# unicorn_1.net
KiCad netlist of a schematic drawn in Altium Designer
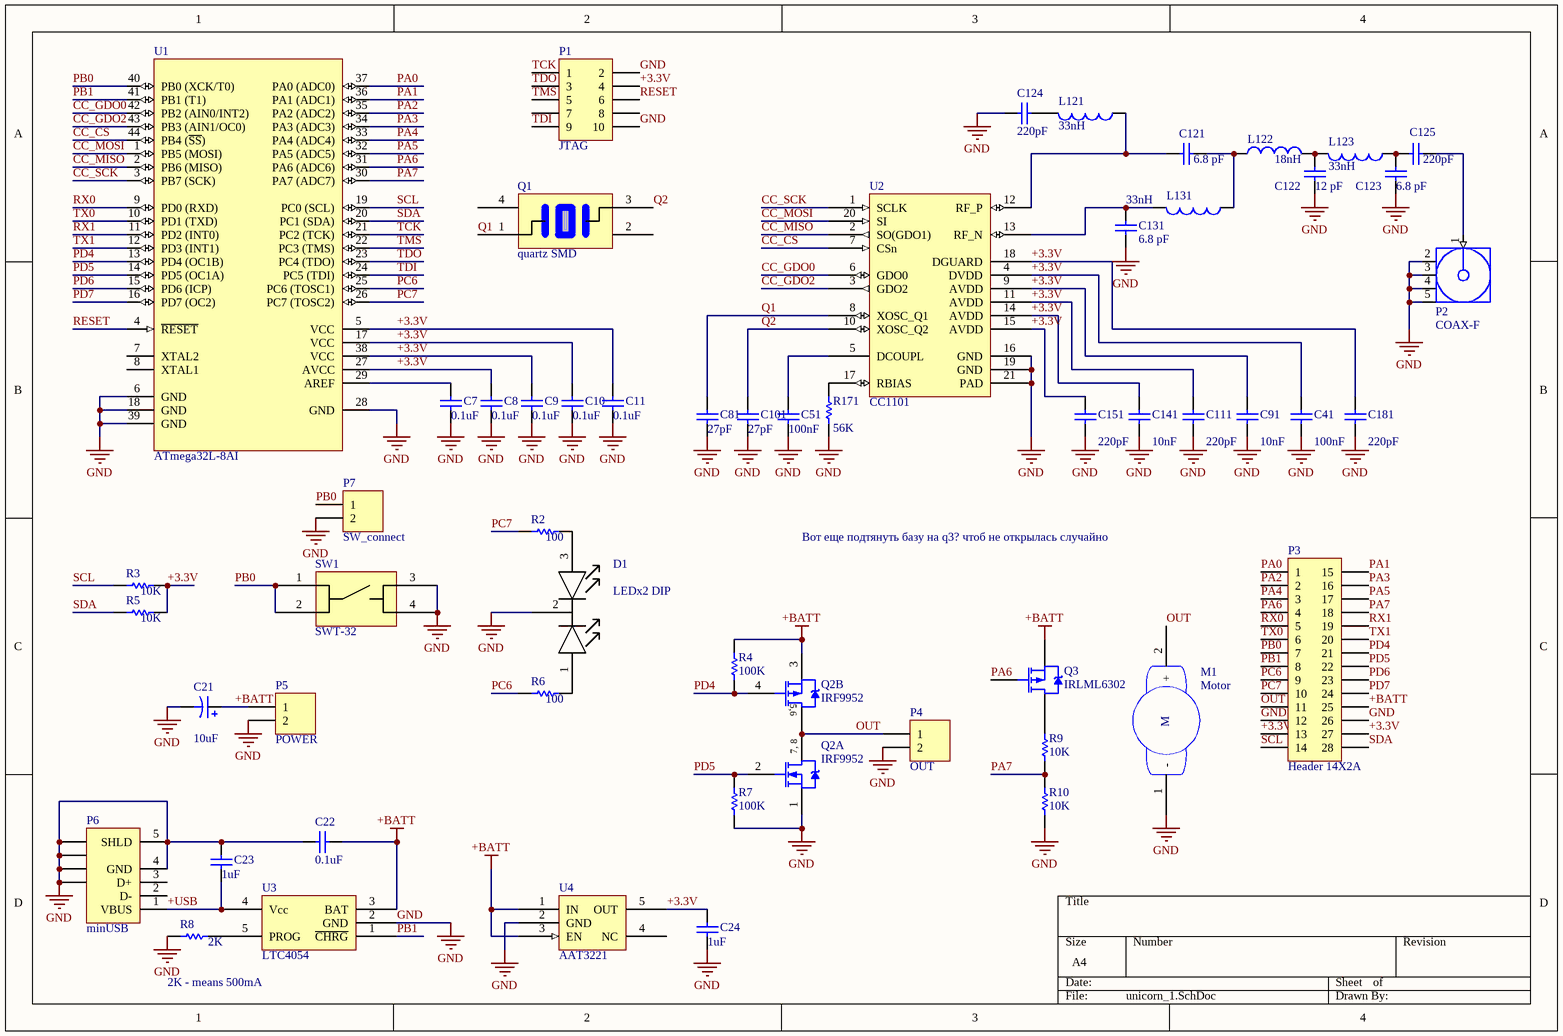
[diagram p0: unicorn_1.SchDoc]

(export (version "E")
  (design (tool "Eeschema 10.0.6"))
  (components
    (comp (ref "C7")
      (value "0.1uF")
      (footprint "CAPC1005L")
      (description "Capacitor (Semiconductor SIM Model)")
      (fields (field (name "Comment") "Cap Semi") (field (name "PUBLISHER") "Altium Limited"))
      (libsource (lib "Miscellaneous Devices") (part "Cap Semi"))
    )
    (comp (ref "C8")
      (value "0.1uF")
      (footprint "CAPC1005L")
      (description "Capacitor (Semiconductor SIM Model)")
      (fields (field (name "Comment") "Cap Semi") (field (name "PUBLISHER") "Altium Limited"))
      (libsource (lib "Miscellaneous Devices") (part "Cap Semi"))
    )
    (comp (ref "C9")
      (value "0.1uF")
      (footprint "CAPC1005L")
      (description "Capacitor (Semiconductor SIM Model)")
      (fields (field (name "Comment") "Cap Semi") (field (name "PUBLISHER") "Altium Limited"))
      (libsource (lib "Miscellaneous Devices") (part "Cap Semi"))
    )
    (comp (ref "C10")
      (value "0.1uF")
      (footprint "CAPC1005L")
      (description "Capacitor (Semiconductor SIM Model)")
      (fields (field (name "Comment") "Cap Semi") (field (name "PUBLISHER") "Altium Limited"))
      (libsource (lib "Miscellaneous Devices") (part "Cap Semi"))
    )
    (comp (ref "C11")
      (value "0.1uF")
      (footprint "CAPC1005L")
      (description "Capacitor (Semiconductor SIM Model)")
      (fields (field (name "Comment") "Cap Semi") (field (name "PUBLISHER") "Altium Limited"))
      (libsource (lib "Miscellaneous Devices") (part "Cap Semi"))
    )
    (comp (ref "C21")
      (value "10uF")
      (footprint "CAPC2012L")
      (description "Polarized Capacitor (Surface Mount)")
      (fields (field (name "Comment") "Cap Pol3") (field (name "PUBLISHER") "Altium Limited"))
      (libsource (lib "Miscellaneous Devices") (part "Cap Pol3"))
    )
    (comp (ref "C22")
      (value "0.1uF")
      (footprint "CAPC1005L")
      (description "Capacitor (Semiconductor SIM Model)")
      (fields (field (name "Comment") "Cap Semi") (field (name "PUBLISHER") "Altium Limited"))
      (libsource (lib "Miscellaneous Devices") (part "Cap Semi"))
    )
    (comp (ref "C23")
      (value "1uF")
      (footprint "CAPC1608L")
      (description "Capacitor (Semiconductor SIM Model)")
      (fields (field (name "Comment") "Cap Semi") (field (name "PUBLISHER") "Altium Limited"))
      (libsource (lib "Miscellaneous Devices") (part "Cap Semi"))
    )
    (comp (ref "C24")
      (value "1uF")
      (footprint "CAPC1608L")
      (description "Capacitor (Semiconductor SIM Model)")
      (fields (field (name "Comment") "Cap Semi") (field (name "PUBLISHER") "Altium Limited"))
      (libsource (lib "Miscellaneous Devices") (part "Cap Semi"))
    )
    (comp (ref "C41")
      (value "100nF")
      (footprint "CAPC1005L")
      (description "Capacitor (Semiconductor SIM Model)")
      (fields (field (name "Comment") "Cap Semi") (field (name "PUBLISHER") "Altium Limited"))
      (libsource (lib "Miscellaneous Devices") (part "Cap Semi"))
    )
    (comp (ref "C51")
      (value "100nF")
      (footprint "CAPC1005L")
      (description "Capacitor (Semiconductor SIM Model)")
      (fields (field (name "Comment") "Cap Semi") (field (name "PUBLISHER") "Altium Limited"))
      (libsource (lib "Miscellaneous Devices") (part "Cap Semi"))
    )
    (comp (ref "C81")
      (value "27pF")
      (footprint "CAPC1005L")
      (description "Capacitor (Semiconductor SIM Model)")
      (fields (field (name "Comment") "Cap Semi") (field (name "PUBLISHER") "Altium Limited"))
      (libsource (lib "Miscellaneous Devices") (part "Cap Semi"))
    )
    (comp (ref "C91")
      (value "10nF")
      (footprint "CAPC1005L")
      (description "Capacitor (Semiconductor SIM Model)")
      (fields (field (name "Comment") "Cap Semi") (field (name "PUBLISHER") "Altium Limited"))
      (libsource (lib "Miscellaneous Devices") (part "Cap Semi"))
    )
    (comp (ref "C101")
      (value "27pF")
      (footprint "CAPC1005L")
      (description "Capacitor (Semiconductor SIM Model)")
      (fields (field (name "Comment") "Cap Semi") (field (name "PUBLISHER") "Altium Limited"))
      (libsource (lib "Miscellaneous Devices") (part "Cap Semi"))
    )
    (comp (ref "C111")
      (value "220pF")
      (footprint "CAPC1005L")
      (description "Capacitor (Semiconductor SIM Model)")
      (fields (field (name "Comment") "Cap Semi") (field (name "PUBLISHER") "Altium Limited"))
      (libsource (lib "Miscellaneous Devices") (part "Cap Semi"))
    )
    (comp (ref "C121")
      (value "6.8 pF")
      (footprint "CAPC1005L")
      (description "Capacitor (Semiconductor SIM Model)")
      (fields (field (name "Comment") "Cap Semi") (field (name "PUBLISHER") "Altium Limited"))
      (libsource (lib "Miscellaneous Devices") (part "Cap Semi"))
    )
    (comp (ref "C122")
      (value "12 pF")
      (footprint "CAPC1005L")
      (description "Capacitor (Semiconductor SIM Model)")
      (fields (field (name "Comment") "Cap Semi") (field (name "PUBLISHER") "Altium Limited"))
      (libsource (lib "Miscellaneous Devices") (part "Cap Semi"))
    )
    (comp (ref "C123")
      (value "6.8 pF")
      (footprint "CAPC1005L")
      (description "Capacitor (Semiconductor SIM Model)")
      (fields (field (name "Comment") "Cap Semi") (field (name "PUBLISHER") "Altium Limited"))
      (libsource (lib "Miscellaneous Devices") (part "Cap Semi"))
    )
    (comp (ref "C124")
      (value "220pF")
      (footprint "CAPC1005L")
      (description "Capacitor (Semiconductor SIM Model)")
      (fields (field (name "Comment") "Cap Semi") (field (name "PUBLISHER") "Altium Limited"))
      (libsource (lib "Miscellaneous Devices") (part "Cap Semi"))
    )
    (comp (ref "C125")
      (value "220pF")
      (footprint "CAPC1005L")
      (description "Capacitor (Semiconductor SIM Model)")
      (fields (field (name "Comment") "Cap Semi") (field (name "PUBLISHER") "Altium Limited"))
      (libsource (lib "Miscellaneous Devices") (part "Cap Semi"))
    )
    (comp (ref "C131")
      (value "6.8 pF")
      (footprint "CAPC1005L")
      (description "Capacitor (Semiconductor SIM Model)")
      (fields (field (name "Comment") "Cap Semi") (field (name "PUBLISHER") "Altium Limited"))
      (libsource (lib "Miscellaneous Devices") (part "Cap Semi"))
    )
    (comp (ref "C141")
      (value "10nF")
      (footprint "CAPC1005L")
      (description "Capacitor (Semiconductor SIM Model)")
      (fields (field (name "Comment") "Cap Semi") (field (name "PUBLISHER") "Altium Limited"))
      (libsource (lib "Miscellaneous Devices") (part "Cap Semi"))
    )
    (comp (ref "C151")
      (value "220pF")
      (footprint "CAPC1005L")
      (description "Capacitor (Semiconductor SIM Model)")
      (fields (field (name "Comment") "Cap Semi") (field (name "PUBLISHER") "Altium Limited"))
      (libsource (lib "Miscellaneous Devices") (part "Cap Semi"))
    )
    (comp (ref "C181")
      (value "220pF")
      (footprint "CAPC1005L")
      (description "Capacitor (Semiconductor SIM Model)")
      (fields (field (name "Comment") "Cap Semi") (field (name "PUBLISHER") "Altium Limited"))
      (libsource (lib "Miscellaneous Devices") (part "Cap Semi"))
    )
    (comp (ref "D1")
      (value "LEDx2 DIP")
      (footprint "LEDx2")
      (description "in DIP")
      (libsource (lib "uni_Library") (part "LEDx2"))
    )
    (comp (ref "L121")
      (value "33nH")
      (footprint "INDC1005AL")
      (description "Inductor")
      (fields (field (name "PUBLISHER") "Altium Limited"))
      (libsource (lib "Miscellaneous Devices") (part "Inductor"))
    )
    (comp (ref "L122")
      (value "18nH")
      (footprint "INDC1005AL")
      (description "Inductor")
      (fields (field (name "PUBLISHER") "Altium Limited"))
      (libsource (lib "Miscellaneous Devices") (part "Inductor"))
    )
    (comp (ref "L123")
      (value "33nH")
      (footprint "INDC1005AL")
      (description "Inductor")
      (fields (field (name "PUBLISHER") "Altium Limited"))
      (libsource (lib "Miscellaneous Devices") (part "Inductor"))
    )
    (comp (ref "L131")
      (value "33nH")
      (footprint "INDC1005AL")
      (description "Inductor")
      (fields (field (name "PUBLISHER") "Altium Limited"))
      (libsource (lib "Miscellaneous Devices") (part "Inductor"))
    )
    (comp (ref "M1") (value "Motor") (footprint "Motor") (libsource (lib "uni_Library") (part "Motor")))
    (comp (ref "P1")
      (value "JTAG")
      (footprint "HDR2X5")
      (description "Header, 5-Pin, Dual row")
      (fields (field (name "PUBLISHER") "Altium Limited"))
      (libsource (lib "Miscellaneous Connectors") (part "Header 5X2"))
    )
    (comp (ref "P2")
      (value "COAX-F")
      (footprint "MCX5.08-H5")
      (fields (field (name "PUBLISHER") "Altium Limited"))
      (libsource (lib "Miscellaneous Connectors") (part "COAX-F"))
    )
    (comp (ref "P3")
      (value "Header 14X2A")
      (footprint "HDR2X14_CEN")
      (description "Header, 14-Pin, Dual row")
      (fields (field (name "PUBLISHER") "Altium Limited"))
      (libsource (lib "Miscellaneous Connectors") (part "Header 14X2A"))
    )
    (comp (ref "P4")
      (value "OUT")
      (footprint "HDR1X2H")
      (description "Header, 2-Pin, Right Angle")
      (fields (field (name "PUBLISHER") "Altium Limited"))
      (libsource (lib "Miscellaneous Connectors") (part "Header 2H"))
    )
    (comp (ref "P5")
      (value "POWER")
      (footprint "HDR1X2H")
      (description "Header, 2-Pin, Right Angle")
      (fields (field (name "PUBLISHER") "Altium Limited"))
      (libsource (lib "Miscellaneous Connectors") (part "Header 2H"))
    )
    (comp (ref "P6")
      (value "minUSB")
      (footprint "440479")
      (description "USB 2.0, Right Angle, SMT, A Type, Receptacle, 5 Position, Black")
      (fields (field (name "PUBLISHER") "Altium Limited"))
      (libsource (lib "AMP Serial Bus USB") (part "440478-2"))
    )
    (comp (ref "P7")
      (value "SW_connect")
      (footprint "HDR1X2")
      (description "Header, 2-Pin")
      (fields (field (name "PUBLISHER") "Altium Limited"))
      (libsource (lib "Miscellaneous Connectors") (part "Header 2"))
    )
    (comp (ref "Q1")
      (value "quartz SMD")
      (footprint "quartz_pattern")
      (description "в корпусе 0532")
      (libsource (lib "uni_Library") (part "qartz 0532"))
    )
    (comp (ref "Q2")
      (value "IRF9952")
      (footprint "SO-8_N")
      (description "HEXFET Power MOSFET")
      (fields (field (name "PUBLISHER") "Altium Limited"))
      (libsource (lib "IR Discrete MOSFET - Power") (part "IRF9952"))
    )
    (comp (ref "Q3")
      (value "IRLML6302")
      (footprint "SOT-23")
      (description "HEXFET Power MOSFET")
      (fields (field (name "PUBLISHER") "Altium Limited"))
      (libsource (lib "IR Discrete MOSFET - Power") (part "IRLML6302"))
    )
    (comp (ref "R2")
      (value "100")
      (footprint "RESC1005L")
      (description "Semiconductor Resistor")
      (fields (field (name "Comment") "Res Semi") (field (name "PUBLISHER") "Altium Limited"))
      (libsource (lib "Miscellaneous Devices") (part "Res Semi"))
    )
    (comp (ref "R3")
      (value "10K")
      (footprint "RESC1005L")
      (description "Semiconductor Resistor")
      (fields (field (name "Comment") "Res Semi") (field (name "PUBLISHER") "Altium Limited"))
      (libsource (lib "Miscellaneous Devices") (part "Res Semi"))
    )
    (comp (ref "R4")
      (value "100K")
      (footprint "RESC1005L")
      (description "Semiconductor Resistor")
      (fields (field (name "Comment") "Res Semi") (field (name "PUBLISHER") "Altium Limited"))
      (libsource (lib "Miscellaneous Devices") (part "Res Semi"))
    )
    (comp (ref "R5")
      (value "10K")
      (footprint "RESC1005L")
      (description "Semiconductor Resistor")
      (fields (field (name "Comment") "Res Semi") (field (name "PUBLISHER") "Altium Limited"))
      (libsource (lib "Miscellaneous Devices") (part "Res Semi"))
    )
    (comp (ref "R6")
      (value "100")
      (footprint "RESC1005L")
      (description "Semiconductor Resistor")
      (fields (field (name "Comment") "Res Semi") (field (name "PUBLISHER") "Altium Limited"))
      (libsource (lib "Miscellaneous Devices") (part "Res Semi"))
    )
    (comp (ref "R7")
      (value "100K")
      (footprint "RESC1005L")
      (description "Semiconductor Resistor")
      (fields (field (name "Comment") "Res Semi") (field (name "PUBLISHER") "Altium Limited"))
      (libsource (lib "Miscellaneous Devices") (part "Res Semi"))
    )
    (comp (ref "R8")
      (value "2K")
      (footprint "RESC1005L")
      (description "Semiconductor Resistor")
      (fields (field (name "Comment") "Res Semi") (field (name "PUBLISHER") "Altium Limited"))
      (libsource (lib "Miscellaneous Devices") (part "Res Semi"))
    )
    (comp (ref "R9")
      (value "10K")
      (footprint "RESC1005L")
      (description "Semiconductor Resistor")
      (fields (field (name "Comment") "Res Semi") (field (name "PUBLISHER") "Altium Limited"))
      (libsource (lib "Miscellaneous Devices") (part "Res Semi"))
    )
    (comp (ref "R10")
      (value "10K")
      (footprint "RESC1005L")
      (description "Semiconductor Resistor")
      (fields (field (name "Comment") "Res Semi") (field (name "PUBLISHER") "Altium Limited"))
      (libsource (lib "Miscellaneous Devices") (part "Res Semi"))
    )
    (comp (ref "R171")
      (value "56K")
      (footprint "RESC1005L")
      (description "Semiconductor Resistor")
      (fields (field (name "Comment") "Res Semi") (field (name "PUBLISHER") "Altium Limited"))
      (libsource (lib "Miscellaneous Devices") (part "Res Semi"))
    )
    (comp (ref "SW1")
      (value "SWT-32")
      (footprint "SWT-32 pattern")
      (description "Кнопка тактова , поверхностный монтаж")
      (libsource (lib "uni_Library") (part "SWT-32"))
    )
    (comp (ref "U1")
      (value "ATmega32L-8AI")
      (footprint "44A_L")
      (description "8-Bit AVR Microcontroller with 32K Bytes of In-System Programmable Flash Memory")
      (fields (field (name "PUBLISHER") "Altium Limited"))
      (libsource (lib "Atmel Microcontroller 8-Bit AVR") (part "ATmega32L-8AI"))
    )
    (comp (ref "U2")
      (value "CC1101")
      (footprint "QFN50P397X397X80-20N")
      (description "Low-Power Sub-1 GHz RF Transceiver")
      (libsource (lib "uni_Library") (part "CC1101"))
    )
    (comp (ref "U3")
      (value "LTC4054")
      (footprint "SOT95P270X100-5N")
      (description "Standalone Linear  Li-Ion Battery Charger with  Thermal Regulation in ThinSOT")
      (libsource (lib "uni_Library") (part "LTC4054"))
    )
    (comp (ref "U4")
      (value "AAT3221")
      (footprint "SOT95P280X145-5N")
      (description "PowerLinear NanoPower low   dropout (LDO) linear regulator.")
      (libsource (lib "uni_Library") (part "AAT3221"))
    )
  )
  (nets
    (net (code "1") (name "+BATT") (class "Default")
      (node (ref "C21") (pin "1") (pinfunction "1_1") (pintype "passive"))
      (node (ref "C22") (pin "2") (pinfunction "2_2") (pintype "passive"))
      (node (ref "P3") (pin "25") (pinfunction "25_25") (pintype "passive"))
      (node (ref "P5") (pin "1") (pinfunction "1_1") (pintype "passive"))
      (node (ref "Q2") (pin "3") (pinfunction "S2_3") (pintype "passive"))
      (node (ref "Q3") (pin "2") (pinfunction "S_2") (pintype "passive"))
      (node (ref "R4") (pin "1") (pinfunction "1_1") (pintype "passive"))
      (node (ref "U3") (pin "3") (pinfunction "BAT_3") (pintype "passive"))
      (node (ref "U4") (pin "1") (pinfunction "IN_1") (pintype "power_in"))
      (node (ref "U4") (pin "3") (pinfunction "EN_3") (pintype "input"))
    )
    (net (code "2") (name "/+3.3V") (class "Default")
      (node (ref "C10") (pin "1") (pinfunction "1_1") (pintype "passive"))
      (node (ref "C11") (pin "1") (pinfunction "1_1") (pintype "passive"))
      (node (ref "C111") (pin "2") (pinfunction "2_2") (pintype "passive"))
      (node (ref "C141") (pin "2") (pinfunction "2_2") (pintype "passive"))
      (node (ref "C151") (pin "2") (pinfunction "2_2") (pintype "passive"))
      (node (ref "C181") (pin "2") (pinfunction "2_2") (pintype "passive"))
      (node (ref "C24") (pin "1") (pinfunction "1_1") (pintype "passive"))
      (node (ref "C41") (pin "2") (pinfunction "2_2") (pintype "passive"))
      (node (ref "C8") (pin "1") (pinfunction "1_1") (pintype "passive"))
      (node (ref "C9") (pin "1") (pinfunction "1_1") (pintype "passive"))
      (node (ref "C91") (pin "2") (pinfunction "2_2") (pintype "passive"))
      (node (ref "P1") (pin "4") (pinfunction "4_4") (pintype "passive"))
      (node (ref "P3") (pin "13") (pinfunction "13_13") (pintype "passive"))
      (node (ref "P3") (pin "27") (pinfunction "27_27") (pintype "passive"))
      (node (ref "R3") (pin "1") (pinfunction "1_1") (pintype "passive"))
      (node (ref "R5") (pin "1") (pinfunction "1_1") (pintype "passive"))
      (node (ref "U1") (pin "17") (pinfunction "VCC_17") (pintype "power_in"))
      (node (ref "U1") (pin "27") (pinfunction "AVCC_27") (pintype "power_in"))
      (node (ref "U1") (pin "38") (pinfunction "VCC_38") (pintype "power_in"))
      (node (ref "U1") (pin "5") (pinfunction "VCC_5") (pintype "power_in"))
      (node (ref "U2") (pin "11") (pinfunction "AVDD_11") (pintype "power_in"))
      (node (ref "U2") (pin "14") (pinfunction "AVDD_14") (pintype "power_in"))
      (node (ref "U2") (pin "15") (pinfunction "AVDD_15") (pintype "power_in"))
      (node (ref "U2") (pin "18") (pinfunction "DGUARD_18") (pintype "power_in"))
      (node (ref "U2") (pin "4") (pinfunction "DVDD_4") (pintype "power_in"))
      (node (ref "U2") (pin "9") (pinfunction "AVDD_9") (pintype "power_in"))
      (node (ref "U4") (pin "5") (pinfunction "OUT_5") (pintype "power_in"))
    )
    (net (code "3") (name "/+USB") (class "Default")
      (node (ref "C23") (pin "2") (pinfunction "2_2") (pintype "passive"))
      (node (ref "P6") (pin "1") (pinfunction "VBUS_1") (pintype "power_in"))
      (node (ref "U3") (pin "4") (pinfunction "Vcc_4") (pintype "passive"))
    )
    (net (code "4") (name "/CC_CS") (class "Default")
      (node (ref "U1") (pin "44") (pinfunction "PB4_(~{SS})_44") (pintype "bidirectional"))
      (node (ref "U2") (pin "7") (pinfunction "CSn_7") (pintype "input"))
    )
    (net (code "5") (name "/CC_GDO0") (class "Default")
      (node (ref "U1") (pin "42") (pinfunction "PB2_(AIN0/INT2)_42") (pintype "bidirectional"))
      (node (ref "U2") (pin "6") (pinfunction "GDO0_6") (pintype "bidirectional"))
    )
    (net (code "6") (name "/CC_GDO2") (class "Default")
      (node (ref "U1") (pin "43") (pinfunction "PB3_(AIN1/OC0)_43") (pintype "bidirectional"))
      (node (ref "U2") (pin "3") (pinfunction "GDO2_3") (pintype "output"))
    )
    (net (code "7") (name "/CC_MISO") (class "Default")
      (node (ref "U1") (pin "2") (pinfunction "PB6_(MISO)_2") (pintype "bidirectional"))
      (node (ref "U2") (pin "2") (pinfunction "SO(GDO1)_2") (pintype "output"))
    )
    (net (code "8") (name "/CC_MOSI") (class "Default")
      (node (ref "U1") (pin "1") (pinfunction "PB5_(MOSI)_1") (pintype "bidirectional"))
      (node (ref "U2") (pin "20") (pinfunction "SI_20") (pintype "input"))
    )
    (net (code "9") (name "/CC_SCK") (class "Default")
      (node (ref "U1") (pin "3") (pinfunction "PB7_(SCK)_3") (pintype "bidirectional"))
      (node (ref "U2") (pin "1") (pinfunction "SCLK_1") (pintype "input"))
    )
    (net (code "10") (name "/OUT") (class "Default")
      (node (ref "M1") (pin "2") (pinfunction "+_2") (pintype "passive"))
      (node (ref "P3") (pin "11") (pinfunction "11_11") (pintype "passive"))
      (node (ref "P4") (pin "1") (pinfunction "1_1") (pintype "passive"))
      (node (ref "Q2") (pin "5") (pinfunction "D2_5") (pintype "passive"))
      (node (ref "Q2") (pin "6") (pinfunction "D2_6") (pintype "passive"))
      (node (ref "Q2") (pin "7") (pinfunction "D1_7") (pintype "passive"))
      (node (ref "Q2") (pin "8") (pinfunction "D1_8") (pintype "passive"))
    )
    (net (code "11") (name "/PA0") (class "Default")
      (node (ref "P3") (pin "1") (pinfunction "1_1") (pintype "passive"))
      (node (ref "U1") (pin "37") (pinfunction "PA0_(ADC0)_37") (pintype "bidirectional"))
    )
    (net (code "12") (name "/PA1") (class "Default")
      (node (ref "P3") (pin "15") (pinfunction "15_15") (pintype "passive"))
      (node (ref "U1") (pin "36") (pinfunction "PA1_(ADC1)_36") (pintype "bidirectional"))
    )
    (net (code "13") (name "/PA2") (class "Default")
      (node (ref "P3") (pin "2") (pinfunction "2_2") (pintype "passive"))
      (node (ref "U1") (pin "35") (pinfunction "PA2_(ADC2)_35") (pintype "bidirectional"))
    )
    (net (code "14") (name "/PA3") (class "Default")
      (node (ref "P3") (pin "16") (pinfunction "16_16") (pintype "passive"))
      (node (ref "U1") (pin "34") (pinfunction "PA3_(ADC3)_34") (pintype "bidirectional"))
    )
    (net (code "15") (name "/PA4") (class "Default")
      (node (ref "P3") (pin "3") (pinfunction "3_3") (pintype "passive"))
      (node (ref "U1") (pin "33") (pinfunction "PA4_(ADC4)_33") (pintype "bidirectional"))
    )
    (net (code "16") (name "/PA5") (class "Default")
      (node (ref "P3") (pin "17") (pinfunction "17_17") (pintype "passive"))
      (node (ref "U1") (pin "32") (pinfunction "PA5_(ADC5)_32") (pintype "bidirectional"))
    )
    (net (code "17") (name "/PA6") (class "Default")
      (node (ref "P3") (pin "4") (pinfunction "4_4") (pintype "passive"))
      (node (ref "Q3") (pin "1") (pinfunction "G_1") (pintype "passive"))
      (node (ref "U1") (pin "31") (pinfunction "PA6_(ADC6)_31") (pintype "bidirectional"))
    )
    (net (code "18") (name "/PA7") (class "Default")
      (node (ref "P3") (pin "18") (pinfunction "18_18") (pintype "passive"))
      (node (ref "R10") (pin "1") (pinfunction "1_1") (pintype "passive"))
      (node (ref "R9") (pin "2") (pinfunction "2_2") (pintype "passive"))
      (node (ref "U1") (pin "30") (pinfunction "PA7_(ADC7)_30") (pintype "bidirectional"))
    )
    (net (code "19") (name "/PB0") (class "Default")
      (node (ref "P3") (pin "7") (pinfunction "7_7") (pintype "passive"))
      (node (ref "P7") (pin "1") (pinfunction "1_1") (pintype "passive"))
      (node (ref "SW1") (pin "1") (pintype "passive"))
      (node (ref "SW1") (pin "2") (pintype "passive"))
      (node (ref "U1") (pin "40") (pinfunction "PB0_(XCK/T0)_40") (pintype "bidirectional"))
    )
    (net (code "20") (name "/PB1") (class "Default")
      (node (ref "P3") (pin "8") (pinfunction "8_8") (pintype "passive"))
      (node (ref "U1") (pin "41") (pinfunction "PB1_(T1)_41") (pintype "bidirectional"))
      (node (ref "U3") (pin "1") (pinfunction "~{CHRG}_1") (pintype "passive"))
    )
    (net (code "21") (name "/PC6") (class "Default")
      (node (ref "P3") (pin "9") (pinfunction "9_9") (pintype "passive"))
      (node (ref "R6") (pin "2") (pinfunction "2_2") (pintype "passive"))
      (node (ref "U1") (pin "25") (pinfunction "PC6_(TOSC1)_25") (pintype "bidirectional"))
    )
    (net (code "22") (name "/PC7") (class "Default")
      (node (ref "P3") (pin "10") (pinfunction "10_10") (pintype "passive"))
      (node (ref "R2") (pin "2") (pinfunction "2_2") (pintype "passive"))
      (node (ref "U1") (pin "26") (pinfunction "PC7_(TOSC2)_26") (pintype "bidirectional"))
    )
    (net (code "23") (name "/PD4") (class "Default")
      (node (ref "P3") (pin "21") (pinfunction "21_21") (pintype "passive"))
      (node (ref "Q2") (pin "4") (pinfunction "G2_4") (pintype "passive"))
      (node (ref "R4") (pin "2") (pinfunction "2_2") (pintype "passive"))
      (node (ref "U1") (pin "13") (pinfunction "PD4_(OC1B)_13") (pintype "bidirectional"))
    )
    (net (code "24") (name "/PD5") (class "Default")
      (node (ref "P3") (pin "22") (pinfunction "22_22") (pintype "passive"))
      (node (ref "Q2") (pin "2") (pinfunction "G1_2") (pintype "passive"))
      (node (ref "R7") (pin "1") (pinfunction "1_1") (pintype "passive"))
      (node (ref "U1") (pin "14") (pinfunction "PD5_(OC1A)_14") (pintype "bidirectional"))
    )
    (net (code "25") (name "/PD6") (class "Default")
      (node (ref "P3") (pin "23") (pinfunction "23_23") (pintype "passive"))
      (node (ref "U1") (pin "15") (pinfunction "PD6_(ICP)_15") (pintype "bidirectional"))
    )
    (net (code "26") (name "/PD7") (class "Default")
      (node (ref "P3") (pin "24") (pinfunction "24_24") (pintype "passive"))
      (node (ref "U1") (pin "16") (pinfunction "PD7_(OC2)_16") (pintype "bidirectional"))
    )
    (net (code "27") (name "/Q1") (class "Default")
      (node (ref "C81") (pin "2") (pinfunction "2_2") (pintype "passive"))
      (node (ref "Q1") (pin "1") (pintype "passive"))
      (node (ref "U2") (pin "8") (pinfunction "XOSC_Q1_8") (pintype "bidirectional"))
    )
    (net (code "28") (name "/Q2") (class "Default")
      (node (ref "C101") (pin "2") (pinfunction "2_2") (pintype "passive"))
      (node (ref "Q1") (pin "3") (pintype "passive"))
      (node (ref "U2") (pin "10") (pinfunction "XOSC_Q2_10") (pintype "bidirectional"))
    )
    (net (code "29") (name "/RESET") (class "Default")
      (node (ref "P1") (pin "6") (pinfunction "6_6") (pintype "passive"))
      (node (ref "U1") (pin "4") (pinfunction "~{RESET}_4") (pintype "input"))
    )
    (net (code "30") (name "/RX0") (class "Default")
      (node (ref "P3") (pin "5") (pinfunction "5_5") (pintype "passive"))
      (node (ref "U1") (pin "9") (pinfunction "PD0_(RXD)_9") (pintype "bidirectional"))
    )
    (net (code "31") (name "/RX1") (class "Default")
      (node (ref "P3") (pin "19") (pinfunction "19_19") (pintype "passive"))
      (node (ref "U1") (pin "11") (pinfunction "PD2_(INT0)_11") (pintype "bidirectional"))
    )
    (net (code "32") (name "/SCL") (class "Default")
      (node (ref "P3") (pin "14") (pinfunction "14_14") (pintype "passive"))
      (node (ref "R3") (pin "2") (pinfunction "2_2") (pintype "passive"))
      (node (ref "U1") (pin "19") (pinfunction "PC0_(SCL)_19") (pintype "bidirectional"))
    )
    (net (code "33") (name "/SDA") (class "Default")
      (node (ref "P3") (pin "28") (pinfunction "28_28") (pintype "passive"))
      (node (ref "R5") (pin "2") (pinfunction "2_2") (pintype "passive"))
      (node (ref "U1") (pin "20") (pinfunction "PC1_(SDA)_20") (pintype "bidirectional"))
    )
    (net (code "34") (name "/TCK") (class "Default")
      (node (ref "P1") (pin "1") (pinfunction "1_1") (pintype "passive"))
      (node (ref "U1") (pin "21") (pinfunction "PC2_(TCK)_21") (pintype "bidirectional"))
    )
    (net (code "35") (name "/TDI") (class "Default")
      (node (ref "P1") (pin "9") (pinfunction "9_9") (pintype "passive"))
      (node (ref "U1") (pin "24") (pinfunction "PC5_(TDI)_24") (pintype "bidirectional"))
    )
    (net (code "36") (name "/TDO") (class "Default")
      (node (ref "P1") (pin "3") (pinfunction "3_3") (pintype "passive"))
      (node (ref "U1") (pin "23") (pinfunction "PC4_(TDO)_23") (pintype "bidirectional"))
    )
    (net (code "37") (name "/TMS") (class "Default")
      (node (ref "P1") (pin "5") (pinfunction "5_5") (pintype "passive"))
      (node (ref "U1") (pin "22") (pinfunction "PC3_(TMS)_22") (pintype "bidirectional"))
    )
    (net (code "38") (name "/TX0") (class "Default")
      (node (ref "P3") (pin "6") (pinfunction "6_6") (pintype "passive"))
      (node (ref "U1") (pin "10") (pinfunction "PD1_(TXD)_10") (pintype "bidirectional"))
    )
    (net (code "39") (name "/TX1") (class "Default")
      (node (ref "P3") (pin "20") (pinfunction "20_20") (pintype "passive"))
      (node (ref "U1") (pin "12") (pinfunction "PD3_(INT1)_12") (pintype "bidirectional"))
    )
    (net (code "40") (name "GND") (class "Default")
      (node (ref "C10") (pin "2") (pinfunction "2_2") (pintype "passive"))
      (node (ref "C101") (pin "1") (pinfunction "1_1") (pintype "passive"))
      (node (ref "C11") (pin "2") (pinfunction "2_2") (pintype "passive"))
      (node (ref "C111") (pin "1") (pinfunction "1_1") (pintype "passive"))
      (node (ref "C122") (pin "1") (pinfunction "1_1") (pintype "passive"))
      (node (ref "C123") (pin "1") (pinfunction "1_1") (pintype "passive"))
      (node (ref "C124") (pin "2") (pinfunction "2_2") (pintype "passive"))
      (node (ref "C131") (pin "2") (pinfunction "2_2") (pintype "passive"))
      (node (ref "C141") (pin "1") (pinfunction "1_1") (pintype "passive"))
      (node (ref "C151") (pin "1") (pinfunction "1_1") (pintype "passive"))
      (node (ref "C181") (pin "1") (pinfunction "1_1") (pintype "passive"))
      (node (ref "C21") (pin "2") (pinfunction "2_2") (pintype "passive"))
      (node (ref "C22") (pin "1") (pinfunction "1_1") (pintype "passive"))
      (node (ref "C23") (pin "1") (pinfunction "1_1") (pintype "passive"))
      (node (ref "C24") (pin "2") (pinfunction "2_2") (pintype "passive"))
      (node (ref "C41") (pin "1") (pinfunction "1_1") (pintype "passive"))
      (node (ref "C51") (pin "1") (pinfunction "1_1") (pintype "passive"))
      (node (ref "C7") (pin "2") (pinfunction "2_2") (pintype "passive"))
      (node (ref "C8") (pin "2") (pinfunction "2_2") (pintype "passive"))
      (node (ref "C81") (pin "1") (pinfunction "1_1") (pintype "passive"))
      (node (ref "C9") (pin "2") (pinfunction "2_2") (pintype "passive"))
      (node (ref "C91") (pin "1") (pinfunction "1_1") (pintype "passive"))
      (node (ref "D1") (pin "2") (pinfunction "GND_2") (pintype "passive"))
      (node (ref "M1") (pin "1") (pinfunction "-_1") (pintype "passive"))
      (node (ref "P1") (pin "10") (pinfunction "10_10") (pintype "passive"))
      (node (ref "P1") (pin "2") (pinfunction "2_2") (pintype "passive"))
      (node (ref "P2") (pin "2") (pinfunction "GND_2") (pintype "power_in"))
      (node (ref "P2") (pin "3") (pinfunction "GND_3") (pintype "power_in"))
      (node (ref "P2") (pin "4") (pinfunction "GND_4") (pintype "power_in"))
      (node (ref "P2") (pin "5") (pinfunction "GND_5") (pintype "power_in"))
      (node (ref "P3") (pin "12") (pinfunction "12_12") (pintype "passive"))
      (node (ref "P3") (pin "26") (pinfunction "26_26") (pintype "passive"))
      (node (ref "P4") (pin "2") (pinfunction "2_2") (pintype "passive"))
      (node (ref "P5") (pin "2") (pinfunction "2_2") (pintype "passive"))
      (node (ref "P6") (pin "4") (pinfunction "GND_4") (pintype "power_in"))
      (node (ref "P6") (pin "5") (pinfunction "SHLD_5") (pintype "passive"))
      (node (ref "P6") (pin "6") (pinfunction "SHLD_6") (pintype "passive"))
      (node (ref "P6") (pin "7") (pinfunction "SHLD_7") (pintype "passive"))
      (node (ref "P6") (pin "8") (pinfunction "SHLD_8") (pintype "passive"))
      (node (ref "P6") (pin "9") (pinfunction "SHLD_9") (pintype "passive"))
      (node (ref "P7") (pin "2") (pinfunction "2_2") (pintype "passive"))
      (node (ref "Q2") (pin "1") (pinfunction "S1_1") (pintype "passive"))
      (node (ref "R10") (pin "2") (pinfunction "2_2") (pintype "passive"))
      (node (ref "R171") (pin "1") (pinfunction "1_1") (pintype "passive"))
      (node (ref "R7") (pin "2") (pinfunction "2_2") (pintype "passive"))
      (node (ref "R8") (pin "2") (pinfunction "2_2") (pintype "passive"))
      (node (ref "SW1") (pin "3") (pintype "passive"))
      (node (ref "SW1") (pin "4") (pintype "passive"))
      (node (ref "U1") (pin "18") (pinfunction "GND_18") (pintype "power_in"))
      (node (ref "U1") (pin "28") (pinfunction "GND_28") (pintype "power_in"))
      (node (ref "U1") (pin "39") (pinfunction "GND_39") (pintype "power_in"))
      (node (ref "U1") (pin "6") (pinfunction "GND_6") (pintype "power_in"))
      (node (ref "U2") (pin "16") (pinfunction "GND_16") (pintype "power_in"))
      (node (ref "U2") (pin "19") (pinfunction "GND_19") (pintype "power_in"))
      (node (ref "U2") (pin "21") (pinfunction "PAD_21") (pintype "power_in"))
      (node (ref "U3") (pin "2") (pinfunction "GND_2") (pintype "passive"))
      (node (ref "U4") (pin "2") (pinfunction "GND_2") (pintype "power_in"))
    )
    (net (code "41") (name "Net-(C121-Pad1)") (class "Default")
      (node (ref "C121") (pin "1") (pinfunction "1_1") (pintype "passive"))
      (node (ref "L122") (pin "1") (pinfunction "1_1") (pintype "passive"))
      (node (ref "L131") (pin "1") (pinfunction "1_1") (pintype "passive"))
    )
    (net (code "42") (name "Net-(C122-Pad2)") (class "Default")
      (node (ref "C122") (pin "2") (pinfunction "2_2") (pintype "passive"))
      (node (ref "L122") (pin "2") (pinfunction "2_2") (pintype "passive"))
      (node (ref "L123") (pin "2") (pinfunction "2_2") (pintype "passive"))
    )
    (net (code "43") (name "Net-(C123-Pad2)") (class "Default")
      (node (ref "C123") (pin "2") (pinfunction "2_2") (pintype "passive"))
      (node (ref "C125") (pin "2") (pinfunction "2_2") (pintype "passive"))
      (node (ref "L123") (pin "1") (pinfunction "1_1") (pintype "passive"))
    )
    (net (code "44") (name "Net-(C124-Pad1)") (class "Default")
      (node (ref "C124") (pin "1") (pinfunction "1_1") (pintype "passive"))
      (node (ref "L121") (pin "2") (pinfunction "2_2") (pintype "passive"))
    )
    (net (code "45") (name "Net-(D1-G)") (class "Default")
      (node (ref "D1") (pin "1") (pinfunction "G_1") (pintype "passive"))
      (node (ref "R6") (pin "1") (pinfunction "1_1") (pintype "passive"))
    )
    (net (code "46") (name "Net-(D1-R)") (class "Default")
      (node (ref "D1") (pin "3") (pinfunction "R_3") (pintype "passive"))
      (node (ref "R2") (pin "1") (pinfunction "1_1") (pintype "passive"))
    )
    (net (code "47") (name "Net-(P2-Signal)") (class "Default")
      (node (ref "C125") (pin "1") (pinfunction "1_1") (pintype "passive"))
      (node (ref "P2") (pin "1") (pinfunction "Signal_1") (pintype "input"))
    )
    (net (code "48") (name "Net-(Q3-D)") (class "Default")
      (node (ref "Q3") (pin "3") (pinfunction "D_3") (pintype "passive"))
      (node (ref "R9") (pin "1") (pinfunction "1_1") (pintype "passive"))
    )
    (net (code "49") (name "Net-(U1-AREF)") (class "Default")
      (node (ref "C7") (pin "1") (pinfunction "1_1") (pintype "passive"))
      (node (ref "U1") (pin "29") (pinfunction "AREF_29") (pintype "passive"))
    )
    (net (code "50") (name "Net-(U2-DCOUPL)") (class "Default")
      (node (ref "C51") (pin "2") (pinfunction "2_2") (pintype "passive"))
      (node (ref "U2") (pin "5") (pinfunction "DCOUPL_5") (pintype "power_in"))
    )
    (net (code "51") (name "Net-(U2-RBIAS)") (class "Default")
      (node (ref "R171") (pin "2") (pinfunction "2_2") (pintype "passive"))
      (node (ref "U2") (pin "17") (pinfunction "RBIAS_17") (pintype "bidirectional"))
    )
    (net (code "52") (name "Net-(U2-RF_N)") (class "Default")
      (node (ref "C131") (pin "1") (pinfunction "1_1") (pintype "passive"))
      (node (ref "L131") (pin "2") (pinfunction "2_2") (pintype "passive"))
      (node (ref "U2") (pin "13") (pinfunction "RF_N_13") (pintype "bidirectional"))
    )
    (net (code "53") (name "Net-(U2-RF_P)") (class "Default")
      (node (ref "C121") (pin "2") (pinfunction "2_2") (pintype "passive"))
      (node (ref "L121") (pin "1") (pinfunction "1_1") (pintype "passive"))
      (node (ref "U2") (pin "12") (pinfunction "RF_P_12") (pintype "bidirectional"))
    )
    (net (code "54") (name "Net-(U3-PROG)") (class "Default")
      (node (ref "R8") (pin "1") (pinfunction "1_1") (pintype "passive"))
      (node (ref "U3") (pin "5") (pinfunction "PROG_5") (pintype "passive"))
    )
    (net (code "55") (name "unconnected-(P1-Pad7)") (class "Default")
      (node (ref "P1") (pin "7") (pinfunction "7_7") (pintype "passive"))
    )
    (net (code "56") (name "unconnected-(P1-Pad8)") (class "Default")
      (node (ref "P1") (pin "8") (pinfunction "8_8") (pintype "passive"))
    )
    (net (code "57") (name "unconnected-(P6-D+-Pad3)") (class "Default")
      (node (ref "P6") (pin "3") (pinfunction "D+_3") (pintype "passive"))
    )
    (net (code "58") (name "unconnected-(P6-D--Pad2)") (class "Default")
      (node (ref "P6") (pin "2") (pinfunction "D-_2") (pintype "passive"))
    )
    (net (code "59") (name "unconnected-(Q1-Pad2)") (class "Default")
      (node (ref "Q1") (pin "2") (pintype "passive"))
    )
    (net (code "60") (name "unconnected-(Q1-Pad4)") (class "Default")
      (node (ref "Q1") (pin "4") (pintype "passive"))
    )
    (net (code "61") (name "unconnected-(U1-XTAL1-Pad8)") (class "Default")
      (node (ref "U1") (pin "8") (pinfunction "XTAL1_8") (pintype "passive"))
    )
    (net (code "62") (name "unconnected-(U1-XTAL2-Pad7)") (class "Default")
      (node (ref "U1") (pin "7") (pinfunction "XTAL2_7") (pintype "passive"))
    )
    (net (code "63") (name "unconnected-(U4-NC-Pad4)") (class "Default")
      (node (ref "U4") (pin "4") (pinfunction "NC_4") (pintype "passive"))
    )
  )
)
